# BPF_eval.net
KiCad netlist of a schematic drawn in EAGLE
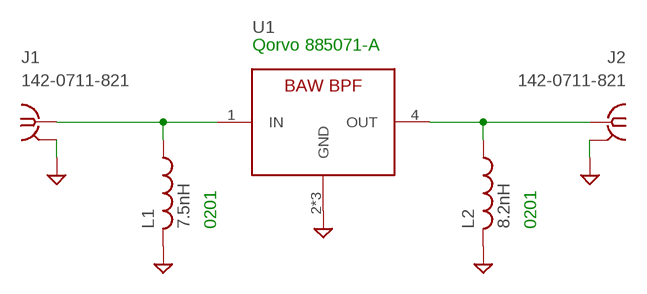
[diagram p0: schematic, sheet 1]

(export (version "E")
  (design (tool "Eeschema 10.0.6"))
  (components
    (comp (ref "J1")
      (value "142-0711-821")
      (footprint "eagle-import:J502-ND-142-0711-821_826")
      (fields (field (name "MF") "JOHNSON COMPONENTS"))
      (libsource (lib "eagle-import") (part "SMA-142-0711-821/826"))
    )
    (comp (ref "J2")
      (value "142-0711-821")
      (footprint "eagle-import:J502-ND-142-0711-821_826")
      (fields (field (name "MF") "JOHNSON COMPONENTS"))
      (libsource (lib "eagle-import") (part "SMA-142-0711-821/826"))
    )
    (comp (ref "L1")
      (value "7.5nH")
      (footprint "eagle-import:L0201")
      (libsource (lib "eagle-import") (part "L-USL0201"))
    )
    (comp (ref "L2")
      (value "8.2nH")
      (footprint "eagle-import:L0201")
      (libsource (lib "eagle-import") (part "L-USL0201"))
    )
    (comp (ref "U1")
      (value "885071-A")
      (footprint "eagle-import:FIL_B39162B9417K610")
      (libsource (lib "eagle-import") (part "885071-A"))
    )
  )
  (nets
    (net (code "1") (name "GND") (class "Default")
      (node (ref "J1") (pin "G@1") (pinfunction "2_G@1") (pintype "passive"))
      (node (ref "J1") (pin "G@2") (pinfunction "2_G@2") (pintype "passive"))
      (node (ref "J1") (pin "G@3") (pinfunction "2_G@3") (pintype "passive"))
      (node (ref "J1") (pin "G@4") (pinfunction "2_G@4") (pintype "passive"))
      (node (ref "J2") (pin "G@1") (pinfunction "2_G@1") (pintype "passive"))
      (node (ref "J2") (pin "G@2") (pinfunction "2_G@2") (pintype "passive"))
      (node (ref "J2") (pin "G@3") (pinfunction "2_G@3") (pintype "passive"))
      (node (ref "J2") (pin "G@4") (pinfunction "2_G@4") (pintype "passive"))
      (node (ref "L1") (pin "2") (pinfunction "2_2") (pintype "passive"))
      (node (ref "L2") (pin "2") (pinfunction "2_2") (pintype "passive"))
      (node (ref "U1") (pin "2") (pinfunction "GND_2") (pintype "power_in"))
      (node (ref "U1") (pin "3") (pinfunction "GND_3") (pintype "power_in"))
      (node (ref "U1") (pin "5") (pinfunction "GND_5") (pintype "power_in"))
    )
    (net (code "2") (name "Net-(U1-IN)") (class "Default")
      (node (ref "J1") (pin "1") (pinfunction "1_1") (pintype "passive"))
      (node (ref "L1") (pin "1") (pinfunction "1_1") (pintype "passive"))
      (node (ref "U1") (pin "1") (pinfunction "IN_1") (pintype "passive"))
    )
    (net (code "3") (name "Net-(U1-OUT)") (class "Default")
      (node (ref "J2") (pin "1") (pinfunction "1_1") (pintype "passive"))
      (node (ref "L2") (pin "1") (pinfunction "1_1") (pintype "passive"))
      (node (ref "U1") (pin "4") (pinfunction "OUT_4") (pintype "passive"))
    )
  )
)
